# EMG_Interface2.net
KiCad netlist of a schematic drawn in Altium Designer
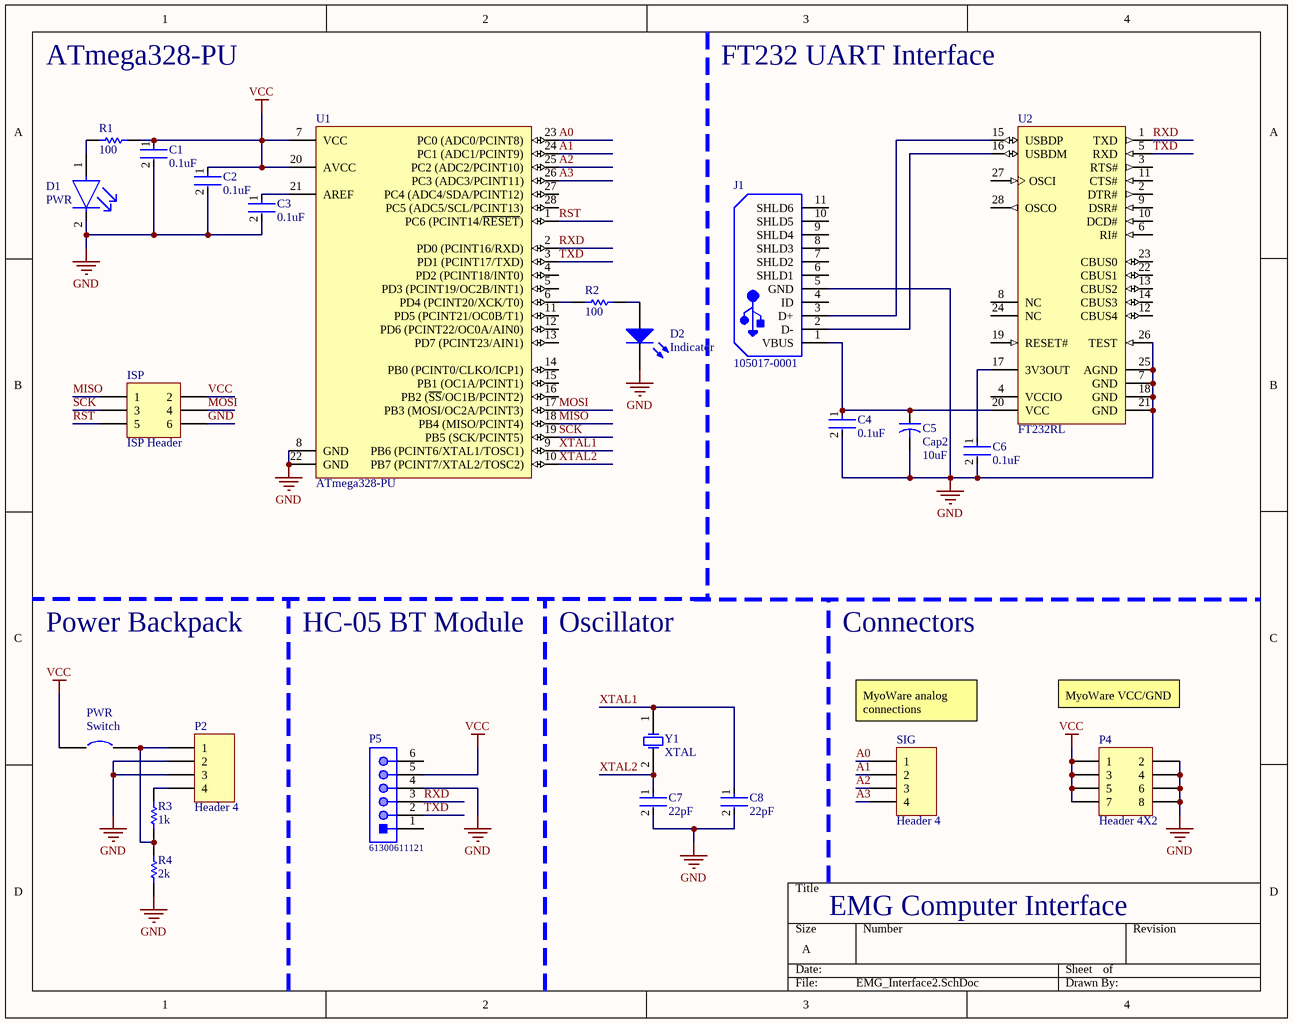
[diagram p0: EMG_Interface2.SchDoc]

(export (version "E")
  (design (tool "Eeschema 10.0.6"))
  (components
    (comp (ref "C1")
      (value "0.1uF")
      (footprint "FP-1206-L_3_2_0_2-W_1_6_0-IPC_C")
      (description "General Purpose Ceramic Capacitor, 1206, 100nF, 5%, X7R, 15%, 100V")
      (fields (field (name "TOLERANCE") "5%") (field (name "VOLTAGE") "100V"))
      (libsource (lib "Altium Content Vault") (part "b4654b650e69147ec39a6b967a45e02"))
    )
    (comp (ref "C2")
      (value "0.1uF")
      (footprint "FP-1206-L_3_2_0_2-W_1_6_0-IPC_C")
      (description "General Purpose Ceramic Capacitor, 1206, 100nF, 5%, X7R, 15%, 100V")
      (fields (field (name "TOLERANCE") "5%") (field (name "VOLTAGE") "100V"))
      (libsource (lib "Altium Content Vault") (part "b4654b650e69147ec39a6b967a45e02"))
    )
    (comp (ref "C3")
      (value "0.1uF")
      (footprint "FP-1206-L_3_2_0_2-W_1_6_0-IPC_C")
      (description "General Purpose Ceramic Capacitor, 1206, 100nF, 5%, X7R, 15%, 100V")
      (fields (field (name "TOLERANCE") "5%") (field (name "VOLTAGE") "100V"))
      (libsource (lib "Altium Content Vault") (part "b4654b650e69147ec39a6b967a45e02"))
    )
    (comp (ref "C4")
      (value "0.1uF")
      (footprint "FP-1206-L_3_2_0_2-W_1_6_0-IPC_C")
      (description "General Purpose Ceramic Capacitor, 1206, 100nF, 5%, X7R, 15%, 100V")
      (fields (field (name "TOLERANCE") "5%") (field (name "VOLTAGE") "100V"))
      (libsource (lib "Altium Content Vault") (part "b4654b650e69147ec39a6b967a45e02"))
    )
    (comp (ref "C5")
      (value "Cap2")
      (footprint "CAPR5-4X5")
      (description "Capacitor")
      (fields (field (name "ALTIUM_VALUE") "10uF") (field (name "PUBLISHER") "Altium Limited"))
      (libsource (lib "Miscellaneous Devices") (part "Cap2"))
    )
    (comp (ref "C6")
      (value "0.1uF")
      (footprint "FP-1206-L_3_2_0_2-W_1_6_0-IPC_C")
      (description "General Purpose Ceramic Capacitor, 1206, 100nF, 5%, X7R, 15%, 100V")
      (fields (field (name "TOLERANCE") "5%") (field (name "VOLTAGE") "100V"))
      (libsource (lib "Altium Content Vault") (part "b4654b650e69147ec39a6b967a45e02"))
    )
    (comp (ref "C7")
      (value "22pF")
      (footprint "FP-C1206C-EB-MFG")
      (description "1206 22pF Ceramic Multilayer Capacitor; 50VDC; 125degC; C0G Dielec; +/-5% SMD")
      (fields
        (field (name "OCTOPART") "https://octopart.com/c1206c220j5gactu-kemet-131912")
        (field (name "TOLERANCE") "0.05")
      )
      (libsource (lib "Altium Content Vault") (part "b4654b650e69147ec39a6b967a45e02"))
    )
    (comp (ref "C8")
      (value "22pF")
      (footprint "FP-C1206C-EB-MFG")
      (description "1206 22pF Ceramic Multilayer Capacitor; 50VDC; 125degC; C0G Dielec; +/-5% SMD")
      (fields
        (field (name "OCTOPART") "https://octopart.com/c1206c220j5gactu-kemet-131912")
        (field (name "TOLERANCE") "0.05")
      )
      (libsource (lib "Altium Content Vault") (part "b4654b650e69147ec39a6b967a45e02"))
    )
    (comp (ref "D1")
      (value "PWR")
      (footprint "FP-SML-LX1206GC-TR-MFG")
      (description "LED GREEN CLEAR 1206 SMD")
      (libsource (lib "Altium Content Vault") (part "ab1c01a81903e929fc6c44469aada92"))
    )
    (comp (ref "D2")
      (value "Indicator")
      (footprint "1206_A")
      (description "SMD mono-color Chip LED, WL-SMCW, Super Red")
      (fields (field (name "MANUFACTURER") "Wuerth Elektronik") (field (name "PARTNUMBER") "150120SS75000"))
      (libsource (lib "Altium Content Vault") (part "WE-LED_K1A2-2"))
    )
    (comp (ref "ISP")
      (value "ISP Header")
      (footprint "HDR2X3")
      (description "Header, 3-Pin, Dual row")
      (fields (field (name "PUBLISHER") "Altium Limited"))
      (libsource (lib "Miscellaneous Connectors") (part "Header 3X2"))
    )
    (comp (ref "J1")
      (value "105017-0001")
      (footprint "USB-MICRO-B_V")
      (fields (field (name "MANUFACTURER") "Molex"))
      (libsource (lib "Altium Content Vault") (part "USB-5-6SHLD"))
    )
    (comp (ref "P2")
      (value "Header 4")
      (footprint "HDR1X4")
      (description "Header, 4-Pin")
      (fields (field (name "PUBLISHER") "Altium Limited"))
      (libsource (lib "Miscellaneous Connectors") (part "Header 4"))
    )
    (comp (ref "P4")
      (value "Header 4X2")
      (footprint "HDR2X4")
      (description "Header, 4-Pin, Dual row")
      (fields (field (name "PUBLISHER") "Altium Limited"))
      (libsource (lib "Miscellaneous Connectors") (part "Header 4X2"))
    )
    (comp (ref "P5")
      (value "61300611121")
      (footprint "61300611121")
      (description "THT Vertical Pin Header WR-PHD, Pitch 2.54 mm, Single Row, 6 pins")
      (fields (field (name "MANUFACTURER") "Wurth Elektronik") (field (name "PUBLISHER") "WurthElektronik"))
      (libsource (lib "Altium Content Vault") (part "WE-CN-1P-M-R6"))
    )
    (comp (ref "PWR")
      (value "Switch")
      (footprint "SPST-2")
      (description "Circuit Breaker")
      (fields (field (name "PUBLISHER") "Altium Limited"))
      (libsource (lib "Miscellaneous Devices") (part "Circuit Breaker"))
    )
    (comp (ref "R1")
      (value "100")
      (footprint "RESC3216X70X50LL05T20")
      (fields (field (name "PART NUMBER") "ERJ-P08J101V") (field (name "MANUFACTURER") "Panasonic"))
      (libsource (lib "Altium Content Vault") (part "RES"))
    )
    (comp (ref "R2")
      (value "100")
      (footprint "RESC3216X70X50LL05T20")
      (fields (field (name "PART NUMBER") "ERJ-P08J101V") (field (name "MANUFACTURER") "Panasonic"))
      (libsource (lib "Altium Content Vault") (part "RES"))
    )
    (comp (ref "R3")
      (value "1k")
      (footprint "RESC3216X70X50LL05T20")
      (fields (field (name "MANUFACTURER") "Panasonic") (field (name "PART NUMBER") "ERJ-8ENF1001V"))
      (libsource (lib "Altium Content Vault") (part "RES"))
    )
    (comp (ref "R4")
      (value "2k")
      (footprint "RESC3216X70X50NL05T20")
      (fields (field (name "PART NUMBER") "ERJ-8ENF2001V") (field (name "MANUFACTURER") "Panasonic"))
      (libsource (lib "Altium Content Vault") (part "RES"))
    )
    (comp (ref "SIG")
      (value "Header 4")
      (footprint "HDR1X4")
      (description "Header, 4-Pin")
      (fields (field (name "PUBLISHER") "Altium Limited"))
      (libsource (lib "Miscellaneous Connectors") (part "Header 4"))
    )
    (comp (ref "U1")
      (value "ATmega328-PU")
      (footprint "28P3")
      (libsource (lib "Altium Content Vault") (part "MC-8B-ATM48-IL28"))
    )
    (comp (ref "U2")
      (value "FT232RL")
      (footprint "FTDI-SSOP-28_M")
      (description "IC USB FS SERIAL UART 28-SSOP")
      (fields (field (name "MANUFACTURER") "FTDI"))
      (libsource (lib "Altium Content Vault") (part "FTDI-FT232-SSOP-28"))
    )
    (comp (ref "Y1")
      (value "XTAL")
      (footprint "R38")
      (description "Crystal Oscillator")
      (fields (field (name "PUBLISHER") "Altium Limited"))
      (libsource (lib "Miscellaneous Devices") (part "XTAL"))
    )
  )
  (nets
    (net (code "1") (name "/A0") (class "Default")
      (node (ref "SIG") (pin "1") (pinfunction "1_1") (pintype "passive"))
      (node (ref "U1") (pin "23") (pinfunction "PC0_(ADC0/PCINT8)_23") (pintype "bidirectional"))
    )
    (net (code "2") (name "/A1") (class "Default")
      (node (ref "SIG") (pin "2") (pinfunction "2_2") (pintype "passive"))
      (node (ref "U1") (pin "24") (pinfunction "PC1_(ADC1/PCINT9)_24") (pintype "bidirectional"))
    )
    (net (code "3") (name "/A2") (class "Default")
      (node (ref "SIG") (pin "3") (pinfunction "3_3") (pintype "passive"))
      (node (ref "U1") (pin "25") (pinfunction "PC2_(ADC2/PCINT10)_25") (pintype "bidirectional"))
    )
    (net (code "4") (name "/A3") (class "Default")
      (node (ref "SIG") (pin "4") (pinfunction "4_4") (pintype "passive"))
      (node (ref "U1") (pin "26") (pinfunction "PC3_(ADC3/PCINT11)_26") (pintype "bidirectional"))
    )
    (net (code "5") (name "/MISO") (class "Default")
      (node (ref "ISP") (pin "1") (pinfunction "1_1") (pintype "passive"))
      (node (ref "U1") (pin "18") (pinfunction "PB4_(MISO/PCINT4)_18") (pintype "bidirectional"))
    )
    (net (code "6") (name "/MOSI") (class "Default")
      (node (ref "ISP") (pin "4") (pinfunction "4_4") (pintype "passive"))
      (node (ref "U1") (pin "17") (pinfunction "PB3_(MOSI/OC2A/PCINT3)_17") (pintype "bidirectional"))
    )
    (net (code "7") (name "/RST") (class "Default")
      (node (ref "ISP") (pin "5") (pinfunction "5_5") (pintype "passive"))
      (node (ref "U1") (pin "1") (pinfunction "PC6_(PCINT14/~{RESET})_1") (pintype "bidirectional"))
    )
    (net (code "8") (name "/RXD") (class "Default")
      (node (ref "P5") (pin "3") (pinfunction "3_3") (pintype "passive"))
      (node (ref "U1") (pin "2") (pinfunction "PD0_(PCINT16/RXD)_2") (pintype "bidirectional"))
      (node (ref "U2") (pin "1") (pinfunction "TXD_1") (pintype "output"))
    )
    (net (code "9") (name "/SCK") (class "Default")
      (node (ref "ISP") (pin "3") (pinfunction "3_3") (pintype "passive"))
      (node (ref "U1") (pin "19") (pinfunction "PB5_(SCK/PCINT5)_19") (pintype "bidirectional"))
    )
    (net (code "10") (name "/TXD") (class "Default")
      (node (ref "P5") (pin "2") (pinfunction "2_2") (pintype "passive"))
      (node (ref "U1") (pin "3") (pinfunction "PD1_(PCINT17/TXD)_3") (pintype "bidirectional"))
      (node (ref "U2") (pin "5") (pinfunction "RXD_5") (pintype "input"))
    )
    (net (code "11") (name "/XTAL1") (class "Default")
      (node (ref "C8") (pin "1") (pinfunction "1_1") (pintype "passive"))
      (node (ref "U1") (pin "9") (pinfunction "PB6_(PCINT6/XTAL1/TOSC1)_9") (pintype "bidirectional"))
      (node (ref "Y1") (pin "1") (pinfunction "OSC1_1") (pintype "passive"))
    )
    (net (code "12") (name "/XTAL2") (class "Default")
      (node (ref "C7") (pin "1") (pinfunction "1_1") (pintype "passive"))
      (node (ref "U1") (pin "10") (pinfunction "PB7_(PCINT7/XTAL2/TOSC2)_10") (pintype "bidirectional"))
      (node (ref "Y1") (pin "2") (pinfunction "OSC2_2") (pintype "passive"))
    )
    (net (code "13") (name "GND") (class "Default")
      (node (ref "C1") (pin "2") (pinfunction "2_2") (pintype "passive"))
      (node (ref "C2") (pin "2") (pinfunction "2_2") (pintype "passive"))
      (node (ref "C3") (pin "2") (pinfunction "2_2") (pintype "passive"))
      (node (ref "C4") (pin "2") (pinfunction "2_2") (pintype "passive"))
      (node (ref "C5") (pin "2") (pinfunction "2_2") (pintype "passive"))
      (node (ref "C6") (pin "2") (pinfunction "2_2") (pintype "passive"))
      (node (ref "C7") (pin "2") (pinfunction "2_2") (pintype "passive"))
      (node (ref "C8") (pin "2") (pinfunction "2_2") (pintype "passive"))
      (node (ref "D1") (pin "2") (pinfunction "C_2") (pintype "passive"))
      (node (ref "D2") (pin "1") (pinfunction "K_1") (pintype "passive"))
      (node (ref "ISP") (pin "6") (pinfunction "6_6") (pintype "passive"))
      (node (ref "J1") (pin "5") (pinfunction "GND_5") (pintype "passive"))
      (node (ref "P2") (pin "2") (pinfunction "2_2") (pintype "passive"))
      (node (ref "P2") (pin "3") (pinfunction "3_3") (pintype "passive"))
      (node (ref "P4") (pin "2") (pinfunction "2_2") (pintype "passive"))
      (node (ref "P4") (pin "4") (pinfunction "4_4") (pintype "passive"))
      (node (ref "P4") (pin "6") (pinfunction "6_6") (pintype "passive"))
      (node (ref "P4") (pin "8") (pinfunction "8_8") (pintype "passive"))
      (node (ref "P5") (pin "4") (pinfunction "4_4") (pintype "passive"))
      (node (ref "R4") (pin "1") (pinfunction "1_1") (pintype "passive"))
      (node (ref "U1") (pin "22") (pinfunction "GND_22") (pintype "power_in"))
      (node (ref "U1") (pin "8") (pinfunction "GND_8") (pintype "power_in"))
      (node (ref "U2") (pin "18") (pinfunction "GND_18") (pintype "power_in"))
      (node (ref "U2") (pin "21") (pinfunction "GND_21") (pintype "power_in"))
      (node (ref "U2") (pin "25") (pinfunction "AGND_25") (pintype "power_in"))
      (node (ref "U2") (pin "26") (pinfunction "TEST_26") (pintype "input"))
      (node (ref "U2") (pin "7") (pinfunction "GND_7") (pintype "power_in"))
    )
    (net (code "14") (name "Net-(D1-A)") (class "Default")
      (node (ref "D1") (pin "1") (pinfunction "A_1") (pintype "passive"))
      (node (ref "R1") (pin "1") (pinfunction "1_1") (pintype "passive"))
    )
    (net (code "15") (name "Net-(D2-A)") (class "Default")
      (node (ref "D2") (pin "2") (pinfunction "A_2") (pintype "passive"))
      (node (ref "R2") (pin "2") (pinfunction "2_2") (pintype "passive"))
    )
    (net (code "16") (name "Net-(J1-D+)") (class "Default")
      (node (ref "J1") (pin "3") (pinfunction "D+_3") (pintype "passive"))
      (node (ref "U2") (pin "15") (pinfunction "USBDP_15") (pintype "bidirectional"))
    )
    (net (code "17") (name "Net-(J1-D-)") (class "Default")
      (node (ref "J1") (pin "2") (pinfunction "D-_2") (pintype "passive"))
      (node (ref "U2") (pin "16") (pinfunction "USBDM_16") (pintype "bidirectional"))
    )
    (net (code "18") (name "Net-(J1-VBUS)") (class "Default")
      (node (ref "C4") (pin "1") (pinfunction "1_1") (pintype "passive"))
      (node (ref "C5") (pin "1") (pinfunction "1_1") (pintype "passive"))
      (node (ref "J1") (pin "1") (pinfunction "VBUS_1") (pintype "passive"))
      (node (ref "U2") (pin "20") (pinfunction "VCC_20") (pintype "power_in"))
    )
    (net (code "19") (name "Net-(P2-Pad1)") (class "Default")
      (node (ref "P2") (pin "1") (pinfunction "1_1") (pintype "passive"))
      (node (ref "PWR") (pin "2") (pinfunction "2_2") (pintype "passive"))
      (node (ref "R3") (pin "1") (pinfunction "1_1") (pintype "passive"))
      (node (ref "R4") (pin "2") (pinfunction "2_2") (pintype "passive"))
    )
    (net (code "20") (name "Net-(P2-Pad4)") (class "Default")
      (node (ref "P2") (pin "4") (pinfunction "4_4") (pintype "passive"))
      (node (ref "R3") (pin "2") (pinfunction "2_2") (pintype "passive"))
    )
    (net (code "21") (name "Net-(U1-AREF)") (class "Default")
      (node (ref "C3") (pin "1") (pinfunction "1_1") (pintype "passive"))
      (node (ref "U1") (pin "21") (pinfunction "AREF_21") (pintype "power_in"))
    )
    (net (code "22") (name "Net-(U1-PD4_(PCINT20{slash}XCK{slash}T0))") (class "Default")
      (node (ref "R2") (pin "1") (pinfunction "1_1") (pintype "passive"))
      (node (ref "U1") (pin "6") (pinfunction "PD4_(PCINT20/XCK/T0)_6") (pintype "bidirectional"))
    )
    (net (code "23") (name "Net-(U2-3V3OUT)") (class "Default")
      (node (ref "C6") (pin "1") (pinfunction "1_1") (pintype "passive"))
      (node (ref "U2") (pin "17") (pinfunction "3V3OUT_17") (pintype "power_in"))
    )
    (net (code "24") (name "VCC") (class "Default")
      (node (ref "C1") (pin "1") (pinfunction "1_1") (pintype "passive"))
      (node (ref "C2") (pin "1") (pinfunction "1_1") (pintype "passive"))
      (node (ref "ISP") (pin "2") (pinfunction "2_2") (pintype "passive"))
      (node (ref "P4") (pin "1") (pinfunction "1_1") (pintype "passive"))
      (node (ref "P4") (pin "3") (pinfunction "3_3") (pintype "passive"))
      (node (ref "P4") (pin "5") (pinfunction "5_5") (pintype "passive"))
      (node (ref "P4") (pin "7") (pinfunction "7_7") (pintype "passive"))
      (node (ref "P5") (pin "5") (pinfunction "5_5") (pintype "passive"))
      (node (ref "PWR") (pin "1") (pinfunction "1_1") (pintype "passive"))
      (node (ref "R1") (pin "2") (pinfunction "2_2") (pintype "passive"))
      (node (ref "U1") (pin "20") (pinfunction "AVCC_20") (pintype "power_in"))
      (node (ref "U1") (pin "7") (pinfunction "VCC_7") (pintype "power_in"))
    )
    (net (code "25") (name "unconnected-(J1-ID-Pad4)") (class "Default")
      (node (ref "J1") (pin "4") (pinfunction "ID_4") (pintype "passive"))
    )
    (net (code "26") (name "unconnected-(J1-SHLD1-Pad6)") (class "Default")
      (node (ref "J1") (pin "6") (pinfunction "SHLD1_6") (pintype "passive"))
    )
    (net (code "27") (name "unconnected-(J1-SHLD2-Pad7)") (class "Default")
      (node (ref "J1") (pin "7") (pinfunction "SHLD2_7") (pintype "passive"))
    )
    (net (code "28") (name "unconnected-(J1-SHLD3-Pad8)") (class "Default")
      (node (ref "J1") (pin "8") (pinfunction "SHLD3_8") (pintype "passive"))
    )
    (net (code "29") (name "unconnected-(J1-SHLD4-Pad9)") (class "Default")
      (node (ref "J1") (pin "9") (pinfunction "SHLD4_9") (pintype "passive"))
    )
    (net (code "30") (name "unconnected-(J1-SHLD5-Pad10)") (class "Default")
      (node (ref "J1") (pin "10") (pinfunction "SHLD5_10") (pintype "passive"))
    )
    (net (code "31") (name "unconnected-(J1-SHLD6-Pad11)") (class "Default")
      (node (ref "J1") (pin "11") (pinfunction "SHLD6_11") (pintype "passive"))
    )
    (net (code "32") (name "unconnected-(P5-Pad1)") (class "Default")
      (node (ref "P5") (pin "1") (pinfunction "1_1") (pintype "passive"))
    )
    (net (code "33") (name "unconnected-(P5-Pad6)") (class "Default")
      (node (ref "P5") (pin "6") (pinfunction "6_6") (pintype "passive"))
    )
    (net (code "34") (name "unconnected-(U1-PB0_(PCINT0{slash}CLKO{slash}ICP1)-Pad14)") (class "Default")
      (node (ref "U1") (pin "14") (pinfunction "PB0_(PCINT0/CLKO/ICP1)_14") (pintype "bidirectional"))
    )
    (net (code "35") (name "unconnected-(U1-PB1_(OC1A{slash}PCINT1)-Pad15)") (class "Default")
      (node (ref "U1") (pin "15") (pinfunction "PB1_(OC1A/PCINT1)_15") (pintype "bidirectional"))
    )
    (net (code "36") (name "unconnected-(U1-PB2_(~{SS}{slash}OC1B{slash}PCINT2)-Pad16)") (class "Default")
      (node (ref "U1") (pin "16") (pinfunction "PB2_(~{SS}/OC1B/PCINT2)_16") (pintype "bidirectional"))
    )
    (net (code "37") (name "unconnected-(U1-PC4_(ADC4{slash}SDA{slash}PCINT12)-Pad27)") (class "Default")
      (node (ref "U1") (pin "27") (pinfunction "PC4_(ADC4/SDA/PCINT12)_27") (pintype "bidirectional"))
    )
    (net (code "38") (name "unconnected-(U1-PC5_(ADC5{slash}SCL{slash}PCINT13)-Pad28)") (class "Default")
      (node (ref "U1") (pin "28") (pinfunction "PC5_(ADC5/SCL/PCINT13)_28") (pintype "bidirectional"))
    )
    (net (code "39") (name "unconnected-(U1-PD2_(PCINT18{slash}INT0)-Pad4)") (class "Default")
      (node (ref "U1") (pin "4") (pinfunction "PD2_(PCINT18/INT0)_4") (pintype "bidirectional"))
    )
    (net (code "40") (name "unconnected-(U1-PD3_(PCINT19{slash}OC2B{slash}INT1)-Pad5)") (class "Default")
      (node (ref "U1") (pin "5") (pinfunction "PD3_(PCINT19/OC2B/INT1)_5") (pintype "bidirectional"))
    )
    (net (code "41") (name "unconnected-(U1-PD5_(PCINT21{slash}OC0B{slash}T1)-Pad11)") (class "Default")
      (node (ref "U1") (pin "11") (pinfunction "PD5_(PCINT21/OC0B/T1)_11") (pintype "bidirectional"))
    )
    (net (code "42") (name "unconnected-(U1-PD6_(PCINT22{slash}OC0A{slash}AIN0)-Pad12)") (class "Default")
      (node (ref "U1") (pin "12") (pinfunction "PD6_(PCINT22/OC0A/AIN0)_12") (pintype "bidirectional"))
    )
    (net (code "43") (name "unconnected-(U1-PD7_(PCINT23{slash}AIN1)-Pad13)") (class "Default")
      (node (ref "U1") (pin "13") (pinfunction "PD7_(PCINT23/AIN1)_13") (pintype "bidirectional"))
    )
    (net (code "44") (name "unconnected-(U2-CBUS0-Pad23)") (class "Default")
      (node (ref "U2") (pin "23") (pinfunction "CBUS0_23") (pintype "bidirectional"))
    )
    (net (code "45") (name "unconnected-(U2-CBUS1-Pad22)") (class "Default")
      (node (ref "U2") (pin "22") (pinfunction "CBUS1_22") (pintype "bidirectional"))
    )
    (net (code "46") (name "unconnected-(U2-CBUS2-Pad13)") (class "Default")
      (node (ref "U2") (pin "13") (pinfunction "CBUS2_13") (pintype "bidirectional"))
    )
    (net (code "47") (name "unconnected-(U2-CBUS3-Pad14)") (class "Default")
      (node (ref "U2") (pin "14") (pinfunction "CBUS3_14") (pintype "bidirectional"))
    )
    (net (code "48") (name "unconnected-(U2-CBUS4-Pad12)") (class "Default")
      (node (ref "U2") (pin "12") (pinfunction "CBUS4_12") (pintype "bidirectional"))
    )
    (net (code "49") (name "unconnected-(U2-CTS#-Pad11)") (class "Default")
      (node (ref "U2") (pin "11") (pinfunction "CTS#_11") (pintype "input"))
    )
    (net (code "50") (name "unconnected-(U2-DCD#-Pad10)") (class "Default")
      (node (ref "U2") (pin "10") (pinfunction "DCD#_10") (pintype "input"))
    )
    (net (code "51") (name "unconnected-(U2-DSR#-Pad9)") (class "Default")
      (node (ref "U2") (pin "9") (pinfunction "DSR#_9") (pintype "input"))
    )
    (net (code "52") (name "unconnected-(U2-DTR#-Pad2)") (class "Default")
      (node (ref "U2") (pin "2") (pinfunction "DTR#_2") (pintype "output"))
    )
    (net (code "53") (name "unconnected-(U2-NC-Pad8)") (class "Default")
      (node (ref "U2") (pin "8") (pinfunction "NC_8") (pintype "passive"))
    )
    (net (code "54") (name "unconnected-(U2-NC-Pad24)") (class "Default")
      (node (ref "U2") (pin "24") (pinfunction "NC_24") (pintype "passive"))
    )
    (net (code "55") (name "unconnected-(U2-OSCI-Pad27)") (class "Default")
      (node (ref "U2") (pin "27") (pinfunction "OSCI_27") (pintype "input"))
    )
    (net (code "56") (name "unconnected-(U2-OSCO-Pad28)") (class "Default")
      (node (ref "U2") (pin "28") (pinfunction "OSCO_28") (pintype "output"))
    )
    (net (code "57") (name "unconnected-(U2-RESET#-Pad19)") (class "Default")
      (node (ref "U2") (pin "19") (pinfunction "RESET#_19") (pintype "input"))
    )
    (net (code "58") (name "unconnected-(U2-RI#-Pad6)") (class "Default")
      (node (ref "U2") (pin "6") (pinfunction "RI#_6") (pintype "input"))
    )
    (net (code "59") (name "unconnected-(U2-RTS#-Pad3)") (class "Default")
      (node (ref "U2") (pin "3") (pinfunction "RTS#_3") (pintype "output"))
    )
    (net (code "60") (name "unconnected-(U2-VCCIO-Pad4)") (class "Default")
      (node (ref "U2") (pin "4") (pinfunction "VCCIO_4") (pintype "power_in"))
    )
  )
)
